# regulated_power_supply_board.net
KiCad netlist of a schematic drawn in Altium Designer
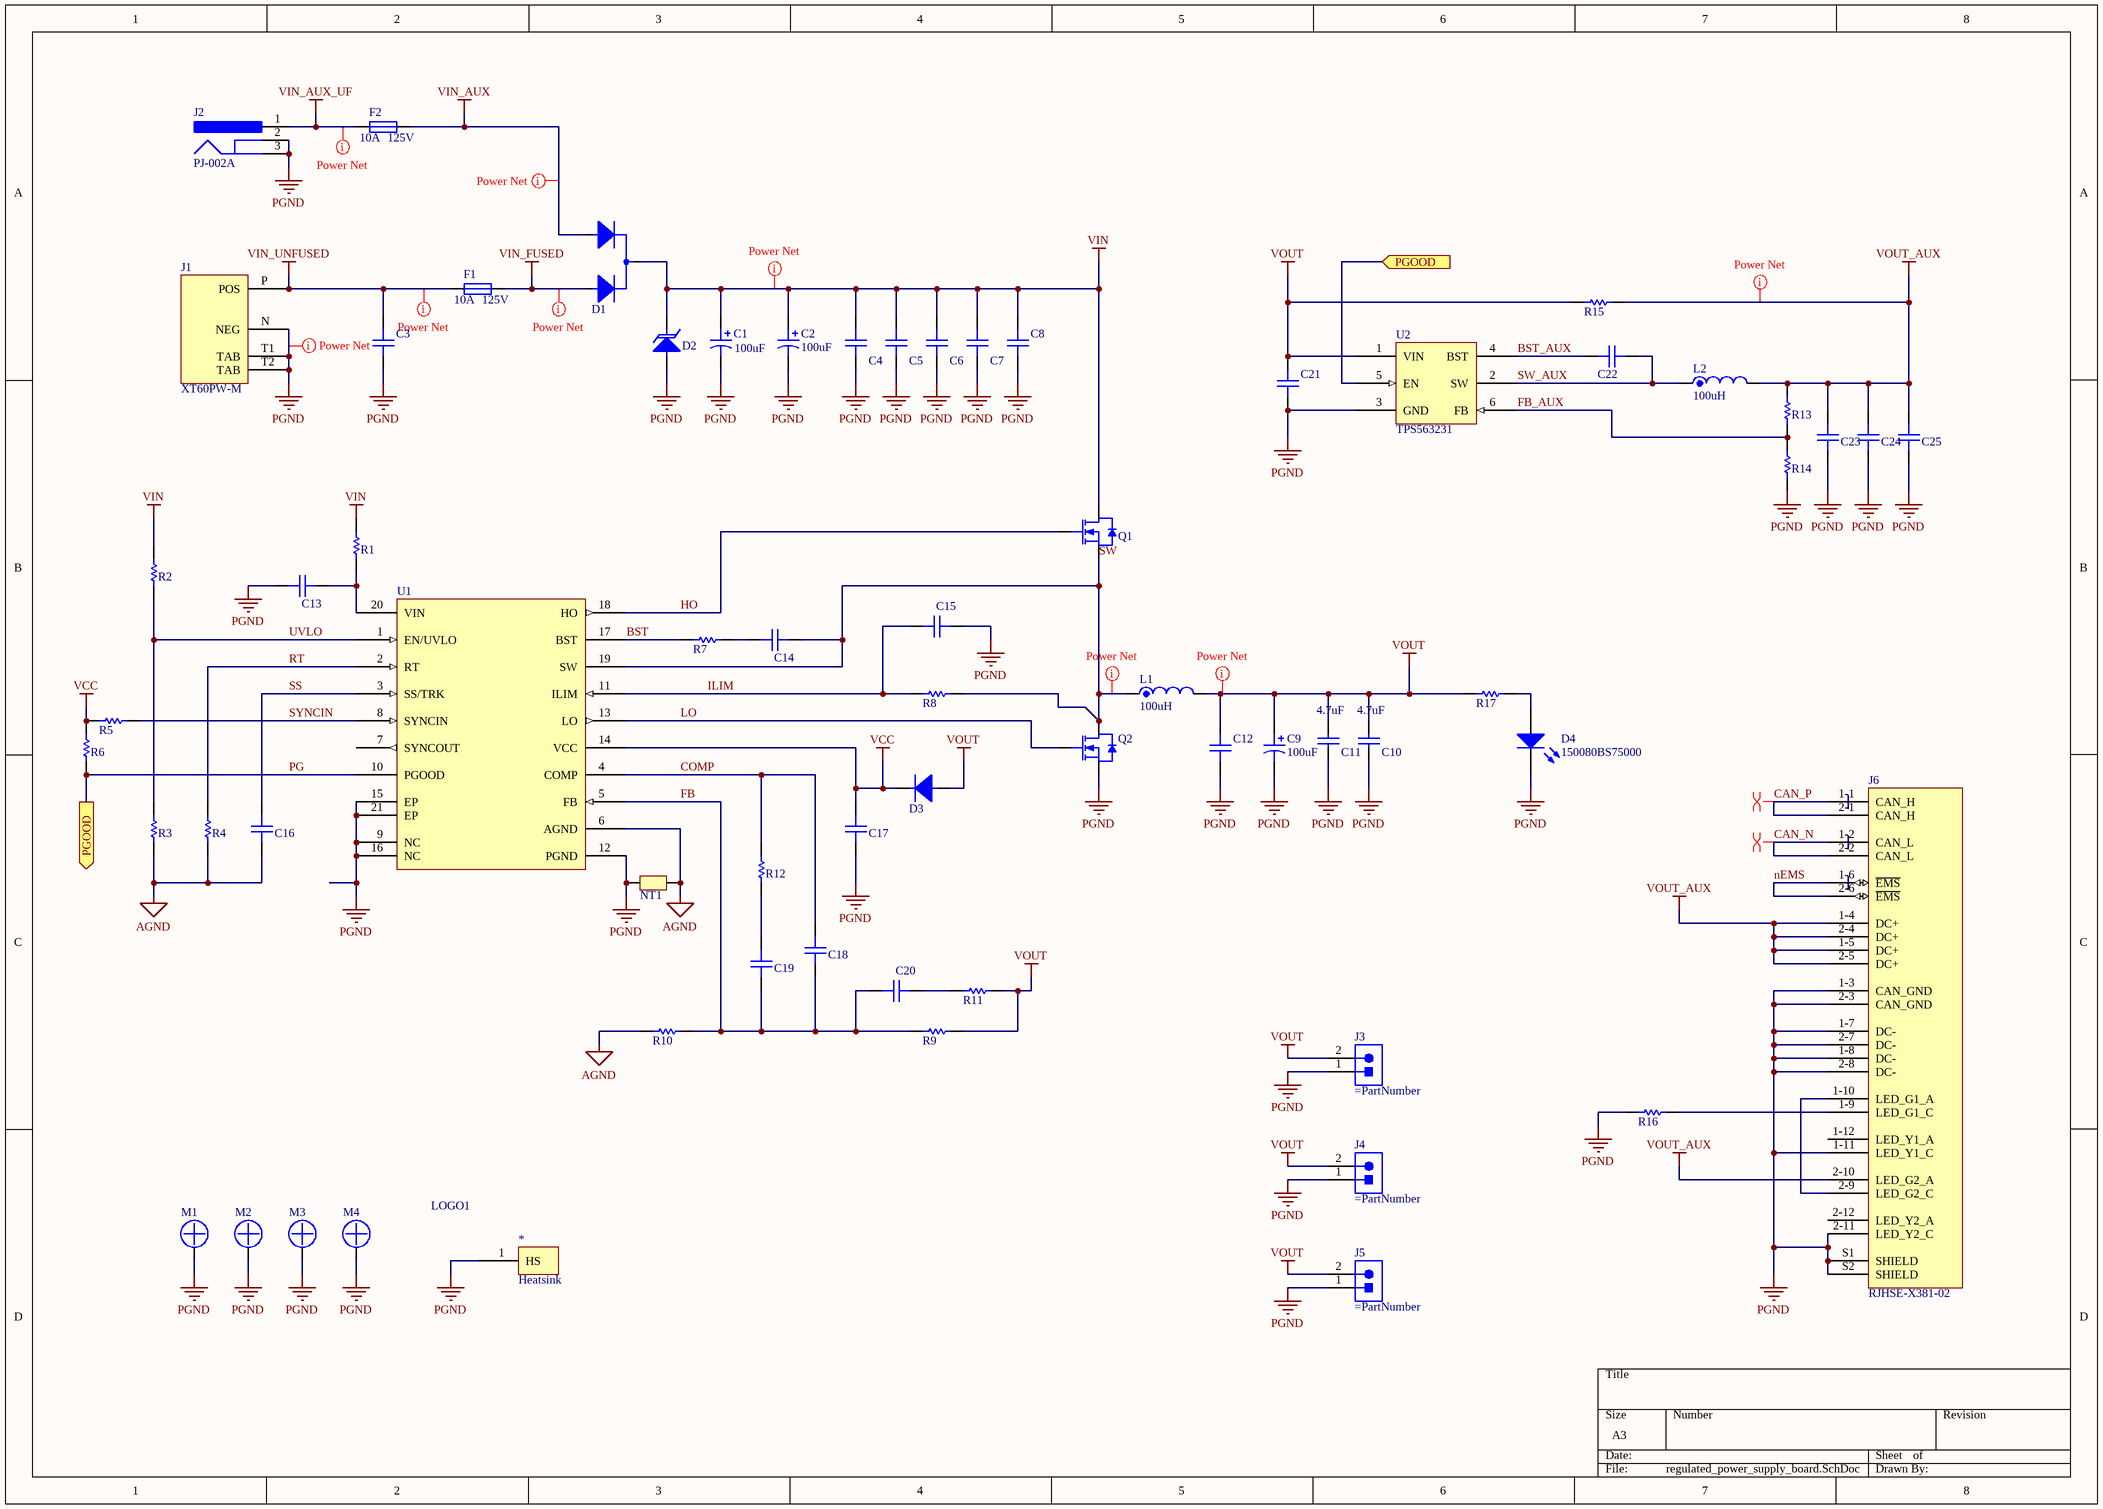
[diagram p0: regulated_power_supply_board.SchDoc]

(export (version "E")
  (design (tool "Eeschema 10.0.6"))
  (components
    (comp (ref "*") (value "Heatsink") (footprint "HS_2510") (libsource (lib "libysk") (part "Heatsink")))
    (comp (ref "C1") (value "100uF") (footprint "CPOL_8x11_5_THRU") (libsource (lib "libysk") (part "CPOL")))
    (comp (ref "C2") (value "100uF") (footprint "CPOL_8x11_5_THRU") (libsource (lib "libysk") (part "CPOL")))
    (comp (ref "C3") (value "~") (footprint "C0603N") (libsource (lib "libysk") (part "C")))
    (comp (ref "C4") (value "~") (footprint "C1210N") (libsource (lib "libysk") (part "C")))
    (comp (ref "C5") (value "~") (footprint "C1210N") (libsource (lib "libysk") (part "C")))
    (comp (ref "C6") (value "~") (footprint "C1210N") (libsource (lib "libysk") (part "C")))
    (comp (ref "C7") (value "~") (footprint "C1210N") (libsource (lib "libysk") (part "C")))
    (comp (ref "C8") (value "~") (footprint "C0603N") (libsource (lib "libysk") (part "C")))
    (comp (ref "C9") (value "100uF") (footprint "CPOL_8x11_5_THRU") (libsource (lib "libysk") (part "CPOL")))
    (comp (ref "C10")
      (value "~")
      (footprint "C1210N")
      (description "Ceramic capacitor 1210 X7R 50V 4.7uF")
      (fields
        (field (name "MANUFACTURER") "Taiyo Yuden")
        (field (name "MANUFACTURER PART NUMBER") "UMK325B7475MM-T")
        (field (name "CAPACITANCE") "4.7uF")
      )
      (libsource (lib "") (part "C_1"))
    )
    (comp (ref "C11")
      (value "~")
      (footprint "C1210N")
      (description "Ceramic capacitor 1210 X7R 50V 4.7uF")
      (fields
        (field (name "MANUFACTURER") "Taiyo Yuden")
        (field (name "MANUFACTURER PART NUMBER") "UMK325B7475MM-T")
        (field (name "CAPACITANCE") "4.7uF")
      )
      (libsource (lib "") (part "C_1"))
    )
    (comp (ref "C12") (value "~") (footprint "C0603N") (libsource (lib "libysk") (part "C")))
    (comp (ref "C13") (value "~") (footprint "C0603N") (libsource (lib "libysk") (part "C")))
    (comp (ref "C14") (value "~") (footprint "C0603N") (libsource (lib "libysk") (part "C")))
    (comp (ref "C15") (value "~") (footprint "C0603N") (libsource (lib "libysk") (part "C")))
    (comp (ref "C16") (value "~") (footprint "C0603N") (libsource (lib "libysk") (part "C")))
    (comp (ref "C17") (value "~") (footprint "C0603N") (libsource (lib "libysk") (part "C")))
    (comp (ref "C18") (value "~") (footprint "C0603N") (libsource (lib "libysk") (part "C")))
    (comp (ref "C19") (value "~") (footprint "C0603N") (libsource (lib "libysk") (part "C")))
    (comp (ref "C20") (value "~") (footprint "C0603N") (libsource (lib "libysk") (part "C")))
    (comp (ref "C21") (value "~") (footprint "C0603N") (libsource (lib "libysk") (part "C")))
    (comp (ref "C22") (value "~") (footprint "C0603N") (libsource (lib "libysk") (part "C")))
    (comp (ref "C23") (value "~") (footprint "C0603N") (libsource (lib "libysk") (part "C")))
    (comp (ref "C24") (value "~") (footprint "C0805N") (libsource (lib "libysk") (part "C")))
    (comp (ref "C25") (value "~") (footprint "C0805N") (libsource (lib "libysk") (part "C")))
    (comp (ref "D1")
      (value "~")
      (footprint "DPAK_JEDEC_N")
      (description "Diode, Common Cathode")
      (libsource (lib "libysk") (part "D_CC"))
    )
    (comp (ref "D2") (value "~") (footprint "SMB") (libsource (lib "libysk") (part "TVS")))
    (comp (ref "D3") (value "~") (footprint "SOD323FLN") (libsource (lib "libysk") (part "D")))
    (comp (ref "D4")
      (value "150080BS75000")
      (footprint "0805_A")
      (description "SMD mono-color Chip LED, WL-SMCW, Blue")
      (fields (field (name "MANUFACTURER") "Wuerth Elektronik"))
      (libsource (lib "Altium Content Vault") (part "WE-LED_K1A2-2"))
    )
    (comp (ref "F1")
      (value "~")
      (footprint "Littelfuse_157")
      (description "FUSE CLIP W/ 10A FUSE, FAST ACTING - More Details")
      (fields
        (field (name "MANUFACTURER") "Littelfuse")
        (field (name "MANUFACTURER PART NUMBER") "0157010.DR")
        (field (name "FUSE CURRENT") "10A")
        (field (name "VOLTAGE RATING (AC)") "125V")
      )
      (libsource (lib "libysk") (part "Littelfuse_157"))
    )
    (comp (ref "F2")
      (value "~")
      (footprint "Littelfuse_157")
      (description "FUSE CLIP W/ 10A FUSE, FAST ACTING - More Details")
      (fields
        (field (name "MANUFACTURER") "Littelfuse")
        (field (name "MANUFACTURER PART NUMBER") "0157010.DR")
        (field (name "FUSE CURRENT") "10A")
        (field (name "VOLTAGE RATING (AC)") "125V")
      )
      (libsource (lib "libysk") (part "Littelfuse_157"))
    )
    (comp (ref "J1")
      (value "XT60PW-M")
      (footprint "XT60PW-M")
      (description "XT60, Male, THT, R/A")
      (libsource (lib "libysk") (part "XT60PW-M"))
    )
    (comp (ref "J2")
      (value "PJ-002A")
      (footprint "CUI-PJ-002A_V")
      (fields (field (name "MANUFACTURER") "CUIInc.") (field (name "MANUFACTURER PART NUMBER") "PJ-002B"))
      (libsource (lib "Altium Content Vault") (part "JACK-2CD3-RN"))
    )
    (comp (ref "J3")
      (value "~")
      (footprint "43045-020X")
      (description "Molex Micro-Fit 3.0, 2POS, R/A w/Pegs, Dual row")
      (libsource (lib "libysk") (part "43045-020X"))
    )
    (comp (ref "J4")
      (value "~")
      (footprint "43045-020X")
      (description "Molex Micro-Fit 3.0, 2POS, R/A w/Pegs, Dual row")
      (libsource (lib "libysk") (part "43045-020X"))
    )
    (comp (ref "J5")
      (value "~")
      (footprint "43045-020X")
      (description "Molex Micro-Fit 3.0, 2POS, R/A w/Pegs, Dual row")
      (libsource (lib "libysk") (part "43045-020X"))
    )
    (comp (ref "J6")
      (value "RJHSE-X381-02")
      (footprint "RJHSE-X38X-02")
      (libsource (lib "libysk") (part "RJHSE-X381-02"))
    )
    (comp (ref "L1") (value "100uH") (footprint "SRP1265A") (libsource (lib "libysk") (part "L")))
    (comp (ref "L2") (value "100uH") (footprint "VLS5045EX_TDK") (libsource (lib "libysk") (part "L")))
    (comp (ref "LOGO1")
      (value "LOGO")
      (footprint "LOGO_designed_by_ysk")
      (libsource (lib "libysk") (part "LOGO"))
    )
    (comp (ref "M1")
      (value "Mounting_Screw")
      (footprint "MOUNT_HOLE_3.2")
      (libsource (lib "libysk") (part "Mounting_Screw"))
    )
    (comp (ref "M2")
      (value "Mounting_Screw")
      (footprint "MOUNT_HOLE_3.2")
      (libsource (lib "libysk") (part "Mounting_Screw"))
    )
    (comp (ref "M3")
      (value "Mounting_Screw")
      (footprint "MOUNT_HOLE_3.2")
      (libsource (lib "libysk") (part "Mounting_Screw"))
    )
    (comp (ref "M4")
      (value "Mounting_Screw")
      (footprint "MOUNT_HOLE_3.2")
      (libsource (lib "libysk") (part "Mounting_Screw"))
    )
    (comp (ref "NT1") (value "Net tie") (footprint "NET_TIE_0_2") (libsource (lib "libysk") (part "NET TIE")))
    (comp (ref "Q1")
      (value "MOSFET-N")
      (footprint "DFN-5 (SO-8FL)")
      (libsource (lib "libysk") (part "MOSFET-N"))
    )
    (comp (ref "Q2")
      (value "MOSFET-N")
      (footprint "DFN-5 (SO-8FL)")
      (libsource (lib "libysk") (part "MOSFET-N"))
    )
    (comp (ref "R1") (value "~") (footprint "R0603N") (libsource (lib "libysk") (part "R")))
    (comp (ref "R2") (value "~") (footprint "R0603N") (libsource (lib "libysk") (part "R")))
    (comp (ref "R3") (value "~") (footprint "R0603N") (libsource (lib "libysk") (part "R")))
    (comp (ref "R4") (value "~") (footprint "R0603N") (libsource (lib "libysk") (part "R")))
    (comp (ref "R5") (value "~") (footprint "R0603N") (libsource (lib "libysk") (part "R")))
    (comp (ref "R6") (value "~") (footprint "R0603N") (libsource (lib "libysk") (part "R")))
    (comp (ref "R7") (value "~") (footprint "R0603N") (libsource (lib "libysk") (part "R")))
    (comp (ref "R8") (value "~") (footprint "R0603N") (libsource (lib "libysk") (part "R")))
    (comp (ref "R9") (value "~") (footprint "R0603N") (libsource (lib "libysk") (part "R")))
    (comp (ref "R10") (value "~") (footprint "R0603N") (libsource (lib "libysk") (part "R")))
    (comp (ref "R11") (value "~") (footprint "R0603N") (libsource (lib "libysk") (part "R")))
    (comp (ref "R12") (value "~") (footprint "R0603N") (libsource (lib "libysk") (part "R")))
    (comp (ref "R13") (value "~") (footprint "R0603N") (libsource (lib "libysk") (part "R")))
    (comp (ref "R14") (value "~") (footprint "R0603N") (libsource (lib "libysk") (part "R")))
    (comp (ref "R15") (value "~") (footprint "R1206N") (libsource (lib "libysk") (part "R")))
    (comp (ref "R16") (value "~") (footprint "R0603N") (libsource (lib "libysk") (part "R")))
    (comp (ref "R17") (value "~") (footprint "R0603N") (libsource (lib "libysk") (part "R")))
    (comp (ref "U1") (value "~") (footprint "RGY0020B_TI_N") (libsource (lib "libysk") (part "LM25145")))
    (comp (ref "U2")
      (value "TPS563231")
      (footprint "DRL0006A_TI_N")
      (libsource (lib "libysk") (part "TPS563231"))
    )
  )
  (nets
    (net (code "1") (name "/BST") (class "Default")
      (node (ref "R7") (pin "1") (pinfunction "1_1") (pintype "passive"))
      (node (ref "U1") (pin "17") (pinfunction "BST_17") (pintype "passive"))
    )
    (net (code "2") (name "/BST_AUX") (class "Default")
      (node (ref "C22") (pin "1") (pinfunction "1_1") (pintype "passive"))
      (node (ref "U2") (pin "4") (pinfunction "BST_4") (pintype "passive"))
    )
    (net (code "3") (name "/CAN_N") (class "Default")
      (node (ref "J6") (pin "1-2") (pinfunction "CAN_L_1-2") (pintype "passive"))
      (node (ref "J6") (pin "2-2") (pinfunction "CAN_L_2-2") (pintype "passive"))
    )
    (net (code "4") (name "/CAN_P") (class "Default")
      (node (ref "J6") (pin "1-1") (pinfunction "CAN_H_1-1") (pintype "passive"))
      (node (ref "J6") (pin "2-1") (pinfunction "CAN_H_2-1") (pintype "passive"))
    )
    (net (code "5") (name "/COMP") (class "Default")
      (node (ref "C18") (pin "1") (pinfunction "1_1") (pintype "passive"))
      (node (ref "R12") (pin "2") (pinfunction "2_2") (pintype "passive"))
      (node (ref "U1") (pin "4") (pinfunction "COMP_4") (pintype "passive"))
    )
    (net (code "6") (name "/FB") (class "Default")
      (node (ref "C18") (pin "2") (pinfunction "2_2") (pintype "passive"))
      (node (ref "C19") (pin "2") (pinfunction "2_2") (pintype "passive"))
      (node (ref "C20") (pin "2") (pinfunction "2_2") (pintype "passive"))
      (node (ref "R10") (pin "2") (pinfunction "2_2") (pintype "passive"))
      (node (ref "R9") (pin "1") (pinfunction "1_1") (pintype "passive"))
      (node (ref "U1") (pin "5") (pinfunction "FB_5") (pintype "input"))
    )
    (net (code "7") (name "/FB_AUX") (class "Default")
      (node (ref "R13") (pin "1") (pinfunction "1_1") (pintype "passive"))
      (node (ref "R14") (pin "2") (pinfunction "2_2") (pintype "passive"))
      (node (ref "U2") (pin "6") (pinfunction "FB_6") (pintype "input"))
    )
    (net (code "8") (name "/HO") (class "Default")
      (node (ref "Q1") (pin "G") (pinfunction "G_G") (pintype "passive"))
      (node (ref "U1") (pin "18") (pinfunction "HO_18") (pintype "output"))
    )
    (net (code "9") (name "/ILIM") (class "Default")
      (node (ref "C15") (pin "2") (pinfunction "2_2") (pintype "passive"))
      (node (ref "R8") (pin "1") (pinfunction "1_1") (pintype "passive"))
      (node (ref "U1") (pin "11") (pinfunction "ILIM_11") (pintype "input"))
    )
    (net (code "10") (name "/LO") (class "Default")
      (node (ref "Q2") (pin "G") (pinfunction "G_G") (pintype "passive"))
      (node (ref "U1") (pin "13") (pinfunction "LO_13") (pintype "output"))
    )
    (net (code "11") (name "/PG") (class "Default")
      (node (ref "R6") (pin "1") (pinfunction "1_1") (pintype "passive"))
      (node (ref "U1") (pin "10") (pinfunction "PGOOD_10") (pintype "open_collector"))
      (node (ref "U2") (pin "5") (pinfunction "EN_5") (pintype "input"))
    )
    (net (code "12") (name "/RT") (class "Default")
      (node (ref "R4") (pin "2") (pinfunction "2_2") (pintype "passive"))
      (node (ref "U1") (pin "2") (pinfunction "RT_2") (pintype "input"))
    )
    (net (code "13") (name "/SS") (class "Default")
      (node (ref "C16") (pin "2") (pinfunction "2_2") (pintype "passive"))
      (node (ref "U1") (pin "3") (pinfunction "SS/TRK_3") (pintype "input"))
    )
    (net (code "14") (name "/SW") (class "Default")
      (node (ref "C14") (pin "1") (pinfunction "1_1") (pintype "passive"))
      (node (ref "L1") (pin "1") (pinfunction "1_1") (pintype "passive"))
      (node (ref "Q1") (pin "S") (pinfunction "S_S") (pintype "passive"))
      (node (ref "Q2") (pin "D") (pinfunction "D_D") (pintype "passive"))
      (node (ref "R8") (pin "2") (pinfunction "2_2") (pintype "passive"))
      (node (ref "U1") (pin "19") (pinfunction "SW_19") (pintype "passive"))
    )
    (net (code "15") (name "/SW_AUX") (class "Default")
      (node (ref "C22") (pin "2") (pinfunction "2_2") (pintype "passive"))
      (node (ref "L2") (pin "1") (pinfunction "1_1") (pintype "passive"))
      (node (ref "U2") (pin "2") (pinfunction "SW_2") (pintype "passive"))
    )
    (net (code "16") (name "/SYNCIN") (class "Default")
      (node (ref "R5") (pin "1") (pinfunction "1_1") (pintype "passive"))
      (node (ref "U1") (pin "8") (pinfunction "SYNCIN_8") (pintype "input"))
    )
    (net (code "17") (name "/UVLO") (class "Default")
      (node (ref "R2") (pin "1") (pinfunction "1_1") (pintype "passive"))
      (node (ref "R3") (pin "2") (pinfunction "2_2") (pintype "passive"))
      (node (ref "U1") (pin "1") (pinfunction "EN/UVLO_1") (pintype "input"))
    )
    (net (code "18") (name "/nEMS") (class "Default")
      (node (ref "J6") (pin "1-6") (pinfunction "~{EMS}_1-6") (pintype "bidirectional"))
      (node (ref "J6") (pin "2-6") (pinfunction "~{EMS}_2-6") (pintype "bidirectional"))
    )
    (net (code "19") (name "AGND") (class "Default")
      (node (ref "C16") (pin "1") (pinfunction "1_1") (pintype "passive"))
      (node (ref "NT1") (pin "2") (pinfunction "2_2") (pintype "passive"))
      (node (ref "R10") (pin "1") (pinfunction "1_1") (pintype "passive"))
      (node (ref "R3") (pin "1") (pinfunction "1_1") (pintype "passive"))
      (node (ref "R4") (pin "1") (pinfunction "1_1") (pintype "passive"))
      (node (ref "U1") (pin "6") (pinfunction "AGND_6") (pintype "power_in"))
    )
    (net (code "20") (name "Net-(C14-Pad2)") (class "Default")
      (node (ref "C14") (pin "2") (pinfunction "2_2") (pintype "passive"))
      (node (ref "R7") (pin "2") (pinfunction "2_2") (pintype "passive"))
    )
    (net (code "21") (name "Net-(C19-Pad1)") (class "Default")
      (node (ref "C19") (pin "1") (pinfunction "1_1") (pintype "passive"))
      (node (ref "R12") (pin "1") (pinfunction "1_1") (pintype "passive"))
    )
    (net (code "22") (name "Net-(C20-Pad1)") (class "Default")
      (node (ref "C20") (pin "1") (pinfunction "1_1") (pintype "passive"))
      (node (ref "R11") (pin "1") (pinfunction "1_1") (pintype "passive"))
    )
    (net (code "23") (name "Net-(D4-A)") (class "Default")
      (node (ref "D4") (pin "2") (pinfunction "A_2") (pintype "passive"))
      (node (ref "R17") (pin "1") (pinfunction "1_1") (pintype "passive"))
    )
    (net (code "24") (name "Net-(J6-LED_G1_A)") (class "Default")
      (node (ref "J6") (pin "1-10") (pinfunction "LED_G1_A_1-10") (pintype "passive"))
      (node (ref "J6") (pin "2-9") (pinfunction "LED_G2_C_2-9") (pintype "passive"))
    )
    (net (code "25") (name "Net-(J6-LED_G1_C)") (class "Default")
      (node (ref "J6") (pin "1-9") (pinfunction "LED_G1_C_1-9") (pintype "passive"))
      (node (ref "R16") (pin "1") (pinfunction "1_1") (pintype "passive"))
    )
    (net (code "26") (name "Net-(U1-VIN)") (class "Default")
      (node (ref "C13") (pin "1") (pinfunction "1_1") (pintype "passive"))
      (node (ref "R1") (pin "2") (pinfunction "2_2") (pintype "passive"))
      (node (ref "U1") (pin "20") (pinfunction "VIN_20") (pintype "power_in"))
    )
    (net (code "27") (name "PGND") (class "Default")
      (node (ref "*") (pin "1") (pinfunction "HS_1") (pintype "passive"))
      (node (ref "C1") (pin "2") (pinfunction "2_2") (pintype "passive"))
      (node (ref "C10") (pin "1") (pinfunction "1_1") (pintype "passive"))
      (node (ref "C11") (pin "1") (pinfunction "1_1") (pintype "passive"))
      (node (ref "C12") (pin "2") (pinfunction "2_2") (pintype "passive"))
      (node (ref "C13") (pin "2") (pinfunction "2_2") (pintype "passive"))
      (node (ref "C15") (pin "1") (pinfunction "1_1") (pintype "passive"))
      (node (ref "C17") (pin "1") (pinfunction "1_1") (pintype "passive"))
      (node (ref "C2") (pin "2") (pinfunction "2_2") (pintype "passive"))
      (node (ref "C21") (pin "2") (pinfunction "2_2") (pintype "passive"))
      (node (ref "C23") (pin "2") (pinfunction "2_2") (pintype "passive"))
      (node (ref "C24") (pin "1") (pinfunction "1_1") (pintype "passive"))
      (node (ref "C25") (pin "1") (pinfunction "1_1") (pintype "passive"))
      (node (ref "C3") (pin "2") (pinfunction "2_2") (pintype "passive"))
      (node (ref "C4") (pin "1") (pinfunction "1_1") (pintype "passive"))
      (node (ref "C5") (pin "1") (pinfunction "1_1") (pintype "passive"))
      (node (ref "C6") (pin "1") (pinfunction "1_1") (pintype "passive"))
      (node (ref "C7") (pin "1") (pinfunction "1_1") (pintype "passive"))
      (node (ref "C8") (pin "2") (pinfunction "2_2") (pintype "passive"))
      (node (ref "C9") (pin "2") (pinfunction "2_2") (pintype "passive"))
      (node (ref "D2") (pin "2") (pinfunction "A_2") (pintype "passive"))
      (node (ref "D4") (pin "1") (pinfunction "K_1") (pintype "passive"))
      (node (ref "J1") (pin "N") (pinfunction "NEG_N") (pintype "passive"))
      (node (ref "J1") (pin "T1") (pinfunction "TAB_T1") (pintype "passive"))
      (node (ref "J1") (pin "T2") (pinfunction "TAB_T2") (pintype "passive"))
      (node (ref "J2") (pin "2") (pinfunction "2_2") (pintype "passive"))
      (node (ref "J2") (pin "3") (pinfunction "3_3") (pintype "passive"))
      (node (ref "J3") (pin "1") (pinfunction "1_1") (pintype "passive"))
      (node (ref "J4") (pin "1") (pinfunction "1_1") (pintype "passive"))
      (node (ref "J5") (pin "1") (pinfunction "1_1") (pintype "passive"))
      (node (ref "J6") (pin "1-11") (pinfunction "LED_Y1_C_1-11") (pintype "passive"))
      (node (ref "J6") (pin "1-3") (pinfunction "CAN_GND_1-3") (pintype "passive"))
      (node (ref "J6") (pin "1-7") (pinfunction "DC-_1-7") (pintype "passive"))
      (node (ref "J6") (pin "1-8") (pinfunction "DC-_1-8") (pintype "passive"))
      (node (ref "J6") (pin "2-11") (pinfunction "LED_Y2_C_2-11") (pintype "passive"))
      (node (ref "J6") (pin "2-3") (pinfunction "CAN_GND_2-3") (pintype "passive"))
      (node (ref "J6") (pin "2-7") (pinfunction "DC-_2-7") (pintype "passive"))
      (node (ref "J6") (pin "2-8") (pinfunction "DC-_2-8") (pintype "passive"))
      (node (ref "J6") (pin "S1") (pinfunction "SHIELD_S1") (pintype "passive"))
      (node (ref "J6") (pin "S2") (pinfunction "SHIELD_S2") (pintype "passive"))
      (node (ref "M1") (pin "1") (pinfunction "1_1") (pintype "passive"))
      (node (ref "M2") (pin "1") (pinfunction "1_1") (pintype "passive"))
      (node (ref "M3") (pin "1") (pinfunction "1_1") (pintype "passive"))
      (node (ref "M4") (pin "1") (pinfunction "1_1") (pintype "passive"))
      (node (ref "NT1") (pin "1") (pinfunction "1_1") (pintype "passive"))
      (node (ref "Q2") (pin "S") (pinfunction "S_S") (pintype "passive"))
      (node (ref "R14") (pin "1") (pinfunction "1_1") (pintype "passive"))
      (node (ref "R16") (pin "2") (pinfunction "2_2") (pintype "passive"))
      (node (ref "U1") (pin "12") (pinfunction "PGND_12") (pintype "power_in"))
      (node (ref "U1") (pin "15") (pinfunction "EP_15") (pintype "passive"))
      (node (ref "U1") (pin "16") (pinfunction "NC_16") (pintype "passive"))
      (node (ref "U1") (pin "21") (pinfunction "EP_21") (pintype "passive"))
      (node (ref "U1") (pin "9") (pinfunction "NC_9") (pintype "passive"))
      (node (ref "U2") (pin "3") (pinfunction "GND_3") (pintype "power_in"))
    )
    (net (code "28") (name "VCC") (class "Default")
      (node (ref "C17") (pin "2") (pinfunction "2_2") (pintype "passive"))
      (node (ref "D3") (pin "1") (pinfunction "C_1") (pintype "passive"))
      (node (ref "R5") (pin "2") (pinfunction "2_2") (pintype "passive"))
      (node (ref "R6") (pin "2") (pinfunction "2_2") (pintype "passive"))
      (node (ref "U1") (pin "14") (pinfunction "VCC_14") (pintype "passive"))
    )
    (net (code "29") (name "VIN") (class "Default")
      (node (ref "C1") (pin "1") (pinfunction "1_1") (pintype "passive"))
      (node (ref "C2") (pin "1") (pinfunction "1_1") (pintype "passive"))
      (node (ref "C4") (pin "2") (pinfunction "2_2") (pintype "passive"))
      (node (ref "C5") (pin "2") (pinfunction "2_2") (pintype "passive"))
      (node (ref "C6") (pin "2") (pinfunction "2_2") (pintype "passive"))
      (node (ref "C7") (pin "2") (pinfunction "2_2") (pintype "passive"))
      (node (ref "C8") (pin "1") (pinfunction "1_1") (pintype "passive"))
      (node (ref "D1") (pin "2") (pinfunction "C_2") (pintype "passive"))
      (node (ref "D2") (pin "1") (pinfunction "C_1") (pintype "passive"))
      (node (ref "Q1") (pin "D") (pinfunction "D_D") (pintype "passive"))
      (node (ref "R1") (pin "1") (pinfunction "1_1") (pintype "passive"))
      (node (ref "R2") (pin "2") (pinfunction "2_2") (pintype "passive"))
    )
    (net (code "30") (name "VIN_AUX") (class "Default")
      (node (ref "D1") (pin "3") (pinfunction "A2_3") (pintype "passive"))
      (node (ref "F2") (pin "2") (pinfunction "2_2") (pintype "passive"))
    )
    (net (code "31") (name "VIN_AUX_UF") (class "Default")
      (node (ref "F2") (pin "1") (pinfunction "1_1") (pintype "passive"))
      (node (ref "J2") (pin "1") (pinfunction "1_1") (pintype "passive"))
    )
    (net (code "32") (name "VIN_FUSED") (class "Default")
      (node (ref "D1") (pin "1") (pinfunction "A1_1") (pintype "passive"))
      (node (ref "F1") (pin "2") (pinfunction "2_2") (pintype "passive"))
    )
    (net (code "33") (name "VIN_UNFUSED") (class "Default")
      (node (ref "C3") (pin "1") (pinfunction "1_1") (pintype "passive"))
      (node (ref "F1") (pin "1") (pinfunction "1_1") (pintype "passive"))
      (node (ref "J1") (pin "P") (pinfunction "POS_P") (pintype "passive"))
    )
    (net (code "34") (name "VOUT") (class "Default")
      (node (ref "C10") (pin "2") (pinfunction "2_2") (pintype "passive"))
      (node (ref "C11") (pin "2") (pinfunction "2_2") (pintype "passive"))
      (node (ref "C12") (pin "1") (pinfunction "1_1") (pintype "passive"))
      (node (ref "C21") (pin "1") (pinfunction "1_1") (pintype "passive"))
      (node (ref "C9") (pin "1") (pinfunction "1_1") (pintype "passive"))
      (node (ref "D3") (pin "2") (pinfunction "A_2") (pintype "passive"))
      (node (ref "J3") (pin "2") (pinfunction "2_2") (pintype "passive"))
      (node (ref "J4") (pin "2") (pinfunction "2_2") (pintype "passive"))
      (node (ref "J5") (pin "2") (pinfunction "2_2") (pintype "passive"))
      (node (ref "L1") (pin "2") (pinfunction "2_2") (pintype "passive"))
      (node (ref "R11") (pin "2") (pinfunction "2_2") (pintype "passive"))
      (node (ref "R15") (pin "1") (pinfunction "1_1") (pintype "passive"))
      (node (ref "R17") (pin "2") (pinfunction "2_2") (pintype "passive"))
      (node (ref "R9") (pin "2") (pinfunction "2_2") (pintype "passive"))
      (node (ref "U2") (pin "1") (pinfunction "VIN_1") (pintype "power_in"))
    )
    (net (code "35") (name "VOUT_AUX") (class "Default")
      (node (ref "C23") (pin "1") (pinfunction "1_1") (pintype "passive"))
      (node (ref "C24") (pin "2") (pinfunction "2_2") (pintype "passive"))
      (node (ref "C25") (pin "2") (pinfunction "2_2") (pintype "passive"))
      (node (ref "J6") (pin "1-4") (pinfunction "DC+_1-4") (pintype "passive"))
      (node (ref "J6") (pin "1-5") (pinfunction "DC+_1-5") (pintype "passive"))
      (node (ref "J6") (pin "2-10") (pinfunction "LED_G2_A_2-10") (pintype "passive"))
      (node (ref "J6") (pin "2-4") (pinfunction "DC+_2-4") (pintype "passive"))
      (node (ref "J6") (pin "2-5") (pinfunction "DC+_2-5") (pintype "passive"))
      (node (ref "L2") (pin "2") (pinfunction "2_2") (pintype "passive"))
      (node (ref "R13") (pin "2") (pinfunction "2_2") (pintype "passive"))
      (node (ref "R15") (pin "2") (pinfunction "2_2") (pintype "passive"))
    )
    (net (code "36") (name "unconnected-(J6-LED_Y1_A-Pad1-12)") (class "Default")
      (node (ref "J6") (pin "1-12") (pinfunction "LED_Y1_A_1-12") (pintype "passive"))
    )
    (net (code "37") (name "unconnected-(J6-LED_Y2_A-Pad2-12)") (class "Default")
      (node (ref "J6") (pin "2-12") (pinfunction "LED_Y2_A_2-12") (pintype "passive"))
    )
    (net (code "38") (name "unconnected-(U1-SYNCOUT-Pad7)") (class "Default")
      (node (ref "U1") (pin "7") (pinfunction "SYNCOUT_7") (pintype "output"))
    )
  )
)
